# USB_Hub.net
KiCad netlist of a schematic drawn in Altium Designer
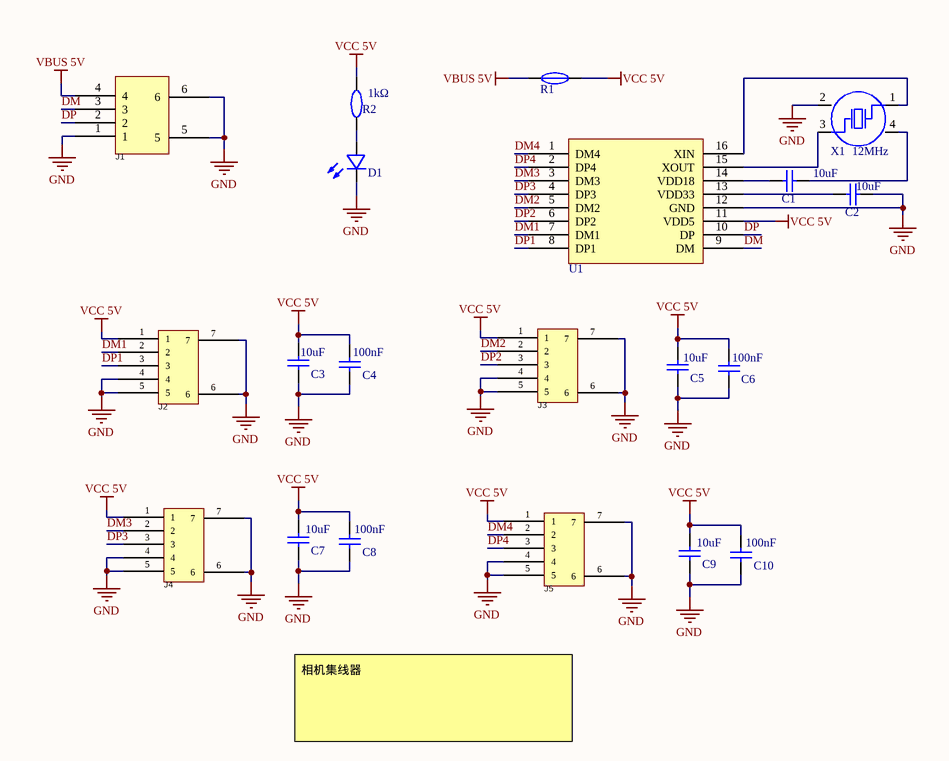
[diagram p0: USB_Hub.SchDoc]

(export (version "E")
  (design (tool "Eeschema 10.0.6"))
  (components
    (comp (ref "C1")
      (value "CAP0805")
      (footprint "C0805")
      (description "0805贴片电容")
      (fields
        (field (name "MANUFACTURER") "SAMSUNG(三星)")
        (field (name "MANUFACTURER PART") "CL21B104KBCNNNC")
      )
      (libsource (lib "Ruixiang_Lib") (part "CAP0805"))
    )
    (comp (ref "C2")
      (value "CAP0805")
      (footprint "C0805")
      (description "0805贴片电容")
      (fields
        (field (name "MANUFACTURER") "SAMSUNG(三星)")
        (field (name "MANUFACTURER PART") "CL21B104KBCNNNC")
      )
      (libsource (lib "Ruixiang_Lib") (part "CAP0805"))
    )
    (comp (ref "C3")
      (value "CAP0805")
      (footprint "C0805")
      (description "0805贴片电容")
      (fields
        (field (name "MANUFACTURER") "SAMSUNG(三星)")
        (field (name "MANUFACTURER PART") "CL21B104KBCNNNC")
      )
      (libsource (lib "Ruixiang_Lib") (part "CAP0805"))
    )
    (comp (ref "C4")
      (value "CAP0805")
      (footprint "C0805")
      (description "0805贴片电容")
      (fields
        (field (name "MANUFACTURER") "SAMSUNG(三星)")
        (field (name "MANUFACTURER PART") "CL21B104KBCNNNC")
      )
      (libsource (lib "Ruixiang_Lib") (part "CAP0805"))
    )
    (comp (ref "C5")
      (value "CAP0805")
      (footprint "C0805")
      (description "0805贴片电容")
      (fields
        (field (name "MANUFACTURER") "SAMSUNG(三星)")
        (field (name "MANUFACTURER PART") "CL21B104KBCNNNC")
      )
      (libsource (lib "Ruixiang_Lib") (part "CAP0805"))
    )
    (comp (ref "C6")
      (value "CAP0805")
      (footprint "C0805")
      (description "0805贴片电容")
      (fields
        (field (name "MANUFACTURER") "SAMSUNG(三星)")
        (field (name "MANUFACTURER PART") "CL21B104KBCNNNC")
      )
      (libsource (lib "Ruixiang_Lib") (part "CAP0805"))
    )
    (comp (ref "C7")
      (value "CAP0805")
      (footprint "C0805")
      (description "0805贴片电容")
      (fields
        (field (name "MANUFACTURER") "SAMSUNG(三星)")
        (field (name "MANUFACTURER PART") "CL21B104KBCNNNC")
      )
      (libsource (lib "Ruixiang_Lib") (part "CAP0805"))
    )
    (comp (ref "C8")
      (value "CAP0805")
      (footprint "C0805")
      (description "0805贴片电容")
      (fields
        (field (name "MANUFACTURER") "SAMSUNG(三星)")
        (field (name "MANUFACTURER PART") "CL21B104KBCNNNC")
      )
      (libsource (lib "Ruixiang_Lib") (part "CAP0805"))
    )
    (comp (ref "C9")
      (value "CAP0805")
      (footprint "C0805")
      (description "0805贴片电容")
      (fields
        (field (name "MANUFACTURER") "SAMSUNG(三星)")
        (field (name "MANUFACTURER PART") "CL21B104KBCNNNC")
      )
      (libsource (lib "Ruixiang_Lib") (part "CAP0805"))
    )
    (comp (ref "C10")
      (value "CAP0805")
      (footprint "C0805")
      (description "0805贴片电容")
      (fields
        (field (name "MANUFACTURER") "SAMSUNG(三星)")
        (field (name "MANUFACTURER PART") "CL21B104KBCNNNC")
      )
      (libsource (lib "Ruixiang_Lib") (part "CAP0805"))
    )
    (comp (ref "D1")
      (value "LED0805-RD")
      (footprint "LED0805-RD")
      (description "蓝光LED")
      (fields (field (name "MANUFACTURER") "MEIHUA(美华科技)") (field (name "MANUFACTURER PART") "MHT170UBCT"))
      (libsource (lib "Ruixiang_Lib") (part "LED0805-RD"))
    )
    (comp (ref "J1")
      (value "AFC01-S04FCC-00")
      (footprint "FFC-SMD_4P-P0.50_AFC01-S04FCC-00")
      (description "4pin FPC接口")
      (fields (field (name "MANUFACTURER") "JS(钜硕电子)"))
      (libsource (lib "Ruixiang_Lib") (part "FPC AFC01-S04FCC-00"))
    )
    (comp (ref "J2")
      (value "WAFER-SH1.0-5PWB")
      (footprint "CONN-SMD_5P-P1.00_XUNPU_WAFER-SH1.0-5PWB")
      (description "SH1.0 5pin 母头端子")
      (fields (field (name "MANUFACTURER") "XUNPU(讯普)"))
      (libsource (lib "Ruixiang_Lib") (part "SH1.0-5pin"))
    )
    (comp (ref "J3")
      (value "WAFER-SH1.0-5PWB")
      (footprint "CONN-SMD_5P-P1.00_XUNPU_WAFER-SH1.0-5PWB")
      (description "SH1.0 5pin 母头端子")
      (fields (field (name "MANUFACTURER") "XUNPU(讯普)"))
      (libsource (lib "Ruixiang_Lib") (part "SH1.0-5pin"))
    )
    (comp (ref "J4")
      (value "WAFER-SH1.0-5PWB")
      (footprint "CONN-SMD_5P-P1.00_XUNPU_WAFER-SH1.0-5PWB")
      (description "SH1.0 5pin 母头端子")
      (fields (field (name "MANUFACTURER") "XUNPU(讯普)"))
      (libsource (lib "Ruixiang_Lib") (part "SH1.0-5pin"))
    )
    (comp (ref "J5")
      (value "WAFER-SH1.0-5PWB")
      (footprint "CONN-SMD_5P-P1.00_XUNPU_WAFER-SH1.0-5PWB")
      (description "SH1.0 5pin 母头端子")
      (fields (field (name "MANUFACTURER") "XUNPU(讯普)"))
      (libsource (lib "Ruixiang_Lib") (part "SH1.0-5pin"))
    )
    (comp (ref "R1")
      (value "TLC F1206")
      (footprint "F1206")
      (description "保险丝")
      (fields (field (name "MANUFACTURER") "TLC(竞沃)") (field (name "MANUFACTURER PART") "TLC-NSMD100"))
      (libsource (lib "Ruixiang_Lib") (part "TLC F1206"))
    )
    (comp (ref "R2")
      (value "RES0805")
      (footprint "R0805")
      (description "0805贴片电阻")
      (fields (field (name "MANUFACTURER") "FH(风华)") (field (name "MANUFACTURER PART") "RS-05K102JT"))
      (libsource (lib "SchLib") (part "RES0805"))
    )
    (comp (ref "U1")
      (value "SL2.1A")
      (footprint "SOP-16_L10.0-W3.9-P1.27-LS6.0-BL")
      (description "USB 2.0接口4口HUB芯片")
      (fields (field (name "MANUFACTURER") "CoreChips(和芯润德)"))
      (libsource (lib "Ruixiang_Lib") (part "SL2.1A"))
    )
    (comp (ref "X1")
      (value "OSC CRYSTAL-SMD_4P-L3.2-W2.5-BL")
      (footprint "CRYSTAL-SMD_4P-L3.2-W2.5-BL")
      (description "晶振")
      (fields (field (name "MANUFACTURER") "JGHC(晶光华)") (field (name "MANUFACTURER PART") "S3212000201080"))
      (libsource (lib "Ruixiang_Lib") (part "OSC CRYSTAL-SMD_4P-L3.2-W2.5-BL"))
    )
  )
  (nets
    (net (code "1") (name "/DM") (class "Default")
      (node (ref "J1") (pin "3") (pinfunction "3_3") (pintype "passive"))
      (node (ref "U1") (pin "9") (pinfunction "DM_9") (pintype "passive"))
    )
    (net (code "2") (name "/DM1") (class "Default")
      (node (ref "J2") (pin "2") (pinfunction "2_2") (pintype "passive"))
      (node (ref "U1") (pin "7") (pinfunction "DM1_7") (pintype "passive"))
    )
    (net (code "3") (name "/DM2") (class "Default")
      (node (ref "J3") (pin "2") (pinfunction "2_2") (pintype "passive"))
      (node (ref "U1") (pin "5") (pinfunction "DM2_5") (pintype "passive"))
    )
    (net (code "4") (name "/DM3") (class "Default")
      (node (ref "J4") (pin "2") (pinfunction "2_2") (pintype "passive"))
      (node (ref "U1") (pin "3") (pinfunction "DM3_3") (pintype "passive"))
    )
    (net (code "5") (name "/DM4") (class "Default")
      (node (ref "J5") (pin "2") (pinfunction "2_2") (pintype "passive"))
      (node (ref "U1") (pin "1") (pinfunction "DM4_1") (pintype "passive"))
    )
    (net (code "6") (name "/DP") (class "Default")
      (node (ref "J1") (pin "2") (pinfunction "2_2") (pintype "passive"))
      (node (ref "U1") (pin "10") (pinfunction "DP_10") (pintype "passive"))
    )
    (net (code "7") (name "/DP1") (class "Default")
      (node (ref "J2") (pin "3") (pinfunction "3_3") (pintype "passive"))
      (node (ref "U1") (pin "8") (pinfunction "DP1_8") (pintype "passive"))
    )
    (net (code "8") (name "/DP2") (class "Default")
      (node (ref "J3") (pin "3") (pinfunction "3_3") (pintype "passive"))
      (node (ref "U1") (pin "6") (pinfunction "DP2_6") (pintype "passive"))
    )
    (net (code "9") (name "/DP3") (class "Default")
      (node (ref "J4") (pin "3") (pinfunction "3_3") (pintype "passive"))
      (node (ref "U1") (pin "4") (pinfunction "DP3_4") (pintype "passive"))
    )
    (net (code "10") (name "/DP4") (class "Default")
      (node (ref "J5") (pin "3") (pinfunction "3_3") (pintype "passive"))
      (node (ref "U1") (pin "2") (pinfunction "DP4_2") (pintype "passive"))
    )
    (net (code "11") (name "GND") (class "Default")
      (node (ref "C10") (pin "1") (pinfunction "1_1") (pintype "passive"))
      (node (ref "C2") (pin "2") (pinfunction "2_2") (pintype "passive"))
      (node (ref "C3") (pin "1") (pinfunction "1_1") (pintype "passive"))
      (node (ref "C4") (pin "1") (pinfunction "1_1") (pintype "passive"))
      (node (ref "C5") (pin "1") (pinfunction "1_1") (pintype "passive"))
      (node (ref "C6") (pin "1") (pinfunction "1_1") (pintype "passive"))
      (node (ref "C7") (pin "1") (pinfunction "1_1") (pintype "passive"))
      (node (ref "C8") (pin "1") (pinfunction "1_1") (pintype "passive"))
      (node (ref "C9") (pin "1") (pinfunction "1_1") (pintype "passive"))
      (node (ref "D1") (pin "1") (pinfunction "-_1") (pintype "passive"))
      (node (ref "J1") (pin "1") (pinfunction "1_1") (pintype "passive"))
      (node (ref "J1") (pin "5") (pinfunction "5_5") (pintype "passive"))
      (node (ref "J1") (pin "6") (pinfunction "6_6") (pintype "passive"))
      (node (ref "J2") (pin "4") (pinfunction "4_4") (pintype "passive"))
      (node (ref "J2") (pin "5") (pinfunction "5_5") (pintype "passive"))
      (node (ref "J2") (pin "6") (pinfunction "6_6") (pintype "passive"))
      (node (ref "J2") (pin "7") (pinfunction "7_7") (pintype "passive"))
      (node (ref "J3") (pin "4") (pinfunction "4_4") (pintype "passive"))
      (node (ref "J3") (pin "5") (pinfunction "5_5") (pintype "passive"))
      (node (ref "J3") (pin "6") (pinfunction "6_6") (pintype "passive"))
      (node (ref "J3") (pin "7") (pinfunction "7_7") (pintype "passive"))
      (node (ref "J4") (pin "4") (pinfunction "4_4") (pintype "passive"))
      (node (ref "J4") (pin "5") (pinfunction "5_5") (pintype "passive"))
      (node (ref "J4") (pin "6") (pinfunction "6_6") (pintype "passive"))
      (node (ref "J4") (pin "7") (pinfunction "7_7") (pintype "passive"))
      (node (ref "J5") (pin "4") (pinfunction "4_4") (pintype "passive"))
      (node (ref "J5") (pin "5") (pinfunction "5_5") (pintype "passive"))
      (node (ref "J5") (pin "6") (pinfunction "6_6") (pintype "passive"))
      (node (ref "J5") (pin "7") (pinfunction "7_7") (pintype "passive"))
      (node (ref "U1") (pin "12") (pinfunction "GND_12") (pintype "passive"))
      (node (ref "X1") (pin "2") (pinfunction "GND_2") (pintype "passive"))
    )
    (net (code "12") (name "Net-(C1-Pad2)") (class "Default")
      (node (ref "C1") (pin "2") (pinfunction "2_2") (pintype "passive"))
      (node (ref "X1") (pin "4") (pinfunction "GND_4") (pintype "passive"))
    )
    (net (code "13") (name "Net-(D1-+)") (class "Default")
      (node (ref "D1") (pin "2") (pinfunction "+_2") (pintype "passive"))
      (node (ref "R2") (pin "1") (pinfunction "1_1") (pintype "passive"))
    )
    (net (code "14") (name "Net-(U1-VDD18)") (class "Default")
      (node (ref "C1") (pin "1") (pinfunction "1_1") (pintype "passive"))
      (node (ref "U1") (pin "14") (pinfunction "VDD18_14") (pintype "passive"))
    )
    (net (code "15") (name "Net-(U1-VDD33)") (class "Default")
      (node (ref "C2") (pin "1") (pinfunction "1_1") (pintype "passive"))
      (node (ref "U1") (pin "13") (pinfunction "VDD33_13") (pintype "passive"))
    )
    (net (code "16") (name "Net-(U1-XIN)") (class "Default")
      (node (ref "U1") (pin "16") (pinfunction "XIN_16") (pintype "passive"))
      (node (ref "X1") (pin "1") (pinfunction "OSC1_1") (pintype "passive"))
    )
    (net (code "17") (name "Net-(U1-XOUT)") (class "Default")
      (node (ref "U1") (pin "15") (pinfunction "XOUT_15") (pintype "passive"))
      (node (ref "X1") (pin "3") (pinfunction "OSC2_3") (pintype "passive"))
    )
    (net (code "18") (name "VBUS 5V") (class "Default")
      (node (ref "J1") (pin "4") (pinfunction "4_4") (pintype "passive"))
      (node (ref "R1") (pin "1") (pinfunction "1_1") (pintype "passive"))
    )
    (net (code "19") (name "VCC 5V") (class "Default")
      (node (ref "C10") (pin "2") (pinfunction "2_2") (pintype "passive"))
      (node (ref "C3") (pin "2") (pinfunction "2_2") (pintype "passive"))
      (node (ref "C4") (pin "2") (pinfunction "2_2") (pintype "passive"))
      (node (ref "C5") (pin "2") (pinfunction "2_2") (pintype "passive"))
      (node (ref "C6") (pin "2") (pinfunction "2_2") (pintype "passive"))
      (node (ref "C7") (pin "2") (pinfunction "2_2") (pintype "passive"))
      (node (ref "C8") (pin "2") (pinfunction "2_2") (pintype "passive"))
      (node (ref "C9") (pin "2") (pinfunction "2_2") (pintype "passive"))
      (node (ref "J2") (pin "1") (pinfunction "1_1") (pintype "passive"))
      (node (ref "J3") (pin "1") (pinfunction "1_1") (pintype "passive"))
      (node (ref "J4") (pin "1") (pinfunction "1_1") (pintype "passive"))
      (node (ref "J5") (pin "1") (pinfunction "1_1") (pintype "passive"))
      (node (ref "R1") (pin "2") (pinfunction "2_2") (pintype "passive"))
      (node (ref "R2") (pin "2") (pinfunction "2_2") (pintype "passive"))
      (node (ref "U1") (pin "11") (pinfunction "VDD5_11") (pintype "passive"))
    )
  )
)
